# Schematic_v13.net
KiCad netlist of a schematic drawn in EAGLE
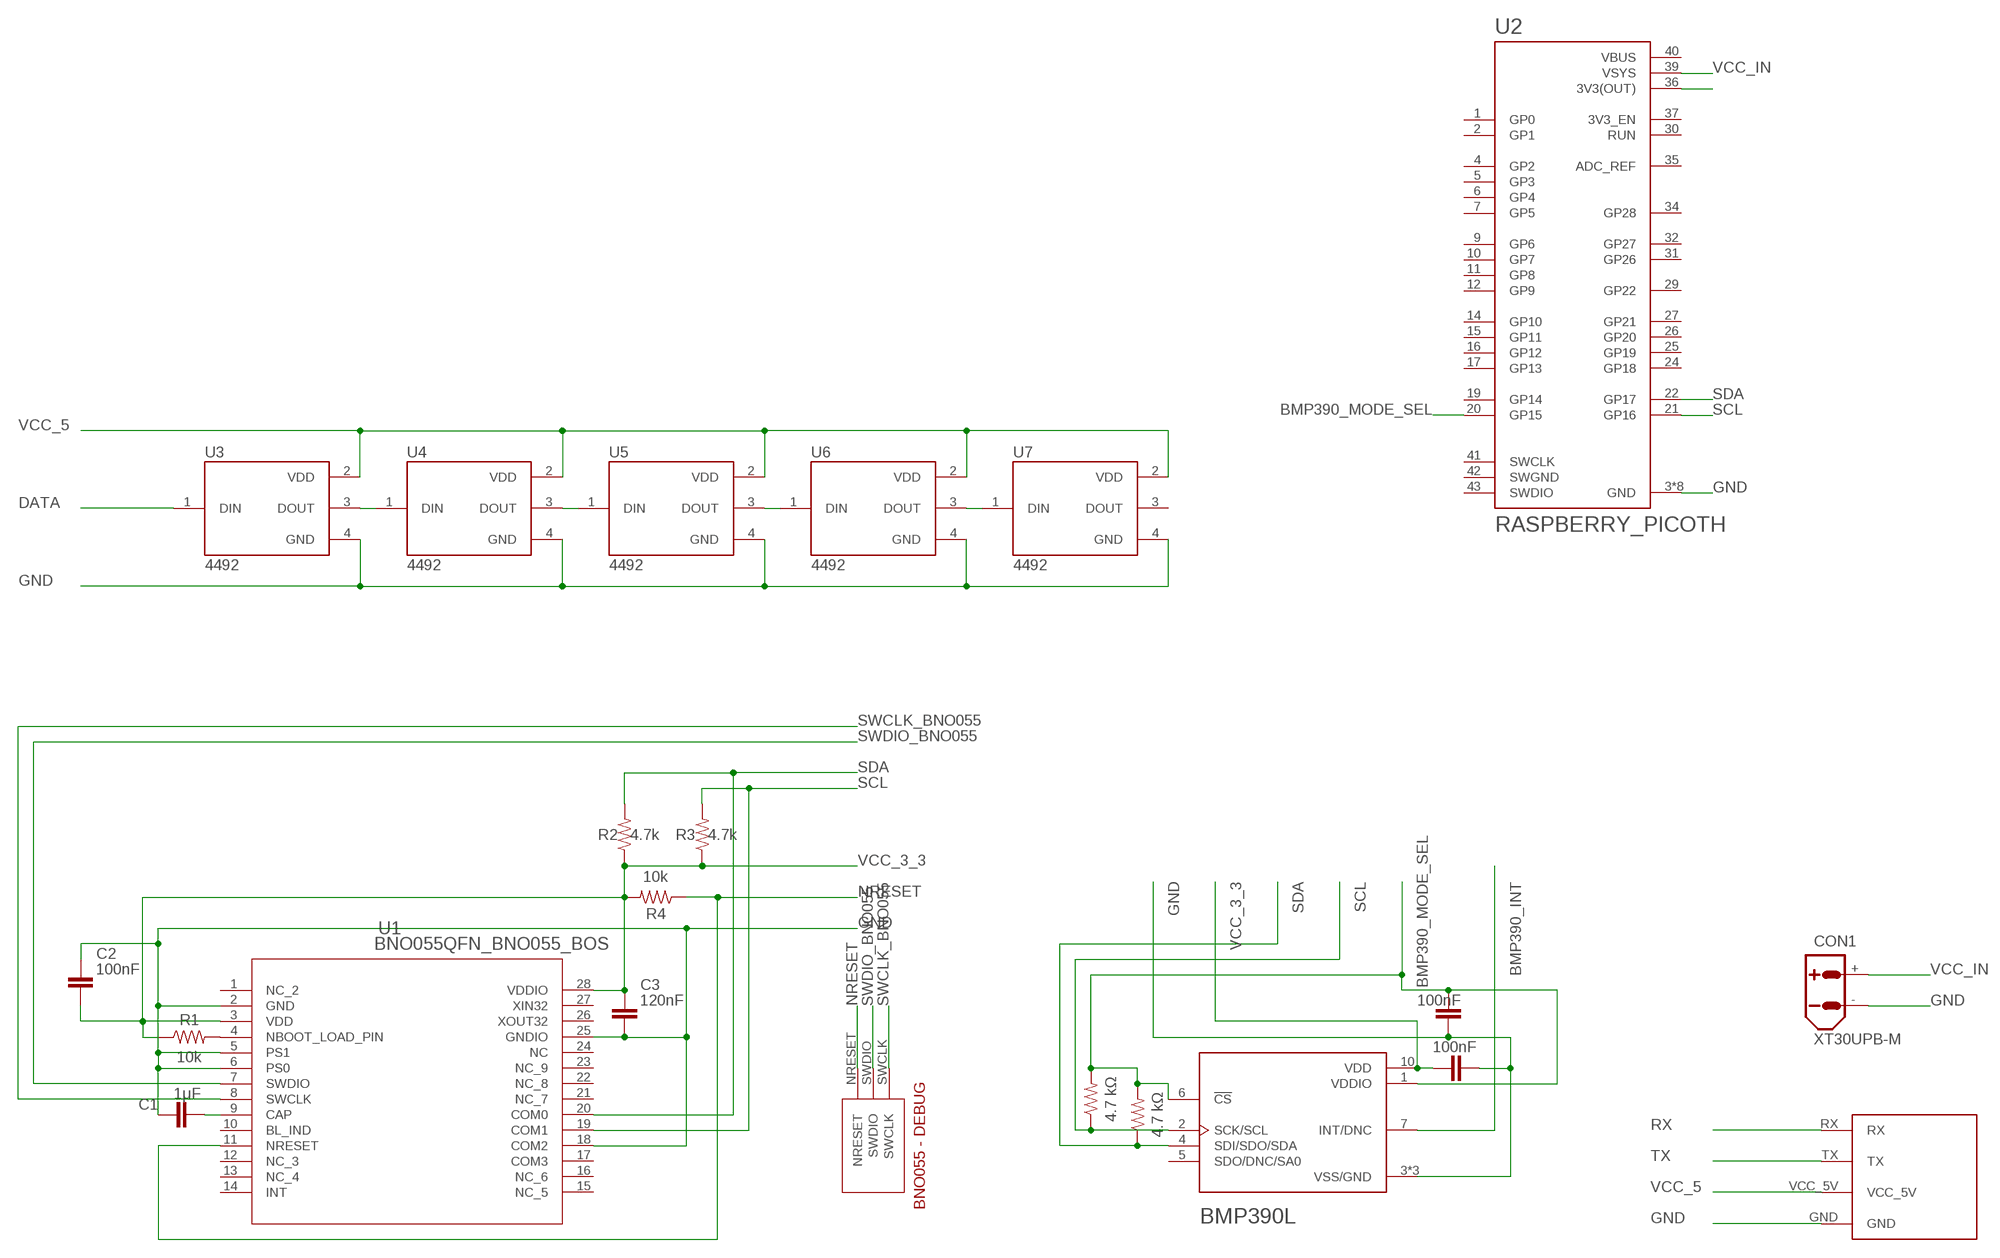
[diagram p0: schematic, sheet 1]

(export (version "E")
  (design (tool "Eeschema 10.0.6"))
  (components
    (comp (ref "C1")
      (value "1μF")
      (footprint "eagle-import:CAPC3216X135")
      (libsource (lib "eagle-import") (part "CCHIP-1206(3216-METRIC)_"))
    )
    (comp (ref "C2")
      (value "100nF")
      (footprint "eagle-import:CAPC3216X135")
      (libsource (lib "eagle-import") (part "CCHIP-1206(3216-METRIC)_"))
    )
    (comp (ref "C3")
      (value "120nF")
      (footprint "eagle-import:CAPC3216X135")
      (libsource (lib "eagle-import") (part "CCHIP-1206(3216-METRIC)_"))
    )
    (comp (ref "C4")
      (value "100nF")
      (footprint "eagle-import:CAPC3216X135")
      (libsource (lib "eagle-import") (part "CCHIP-1206(3216-METRIC)_"))
    )
    (comp (ref "C5")
      (value "100nF")
      (footprint "eagle-import:CAPC3216X135")
      (libsource (lib "eagle-import") (part "CCHIP-1206(3216-METRIC)_"))
    )
    (comp (ref "CON1")
      (value "XT30UPB-M")
      (footprint "eagle-import:XT30UPB-M")
      (libsource (lib "eagle-import") (part "XT30UPB-M"))
    )
    (comp (ref "R1")
      (value "10k")
      (footprint "eagle-import:RESC3216X70")
      (libsource (lib "eagle-import") (part "R-USCHIP-1206(3216-METRIC)_"))
    )
    (comp (ref "R2")
      (value "4.7k")
      (footprint "eagle-import:RESC3216X70")
      (libsource (lib "eagle-import") (part "R-USCHIP-1206(3216-METRIC)_"))
    )
    (comp (ref "R3")
      (value "4.7k")
      (footprint "eagle-import:RESC3216X70")
      (libsource (lib "eagle-import") (part "R-USCHIP-1206(3216-METRIC)_"))
    )
    (comp (ref "R4")
      (value "10k")
      (footprint "eagle-import:RESC3216X70")
      (libsource (lib "eagle-import") (part "R-USCHIP-1206(3216-METRIC)_"))
    )
    (comp (ref "R5")
      (value "4.7 kΩ")
      (footprint "eagle-import:RESC3216X70")
      (libsource (lib "eagle-import") (part "R-USCHIP-1206(3216-METRIC)_"))
    )
    (comp (ref "R6")
      (value "4.7 kΩ")
      (footprint "eagle-import:RESC3216X70")
      (libsource (lib "eagle-import") (part "R-USCHIP-1206(3216-METRIC)_"))
    )
    (comp (ref "U$1")
      (value "EP1")
      (footprint "eagle-import:EP1_MODEL")
      (libsource (lib "eagle-import") (part "EP1"))
    )
    (comp (ref "U$2")
      (value "BNO055_DEBUG_PORT")
      (footprint "eagle-import:BNO05_FOOTPRINT")
      (libsource (lib "eagle-import") (part "BNO055_DEBUG_PORT"))
    )
    (comp (ref "U1")
      (value "BNO055QFN_BNO055_BOS")
      (footprint "eagle-import:QFN_BNO055_BOS")
      (fields
        (field (name "MANUFACTURER_PART_NUMBER") "BNO055")
        (field (name "COPYRIGHT") "Copyright (C) 2024 Ultra Librarian. All rights reserved.")
      )
      (libsource (lib "eagle-import") (part "BNO055QFN_BNO055_BOS"))
    )
    (comp (ref "U2")
      (value "RASPBERRY_PICOTH")
      (footprint "eagle-import:PICO-PKG-TH")
      (libsource (lib "eagle-import") (part "RASPBERRY_PICOTH"))
    )
    (comp (ref "U3")
      (value "4492")
      (footprint "eagle-import:LED_4492")
      (fields (field (name "MF") "Adafruit"))
      (libsource (lib "eagle-import") (part "4492"))
    )
    (comp (ref "U4")
      (value "4492")
      (footprint "eagle-import:LED_4492")
      (fields (field (name "MF") "Adafruit"))
      (libsource (lib "eagle-import") (part "4492"))
    )
    (comp (ref "U5")
      (value "4492")
      (footprint "eagle-import:LED_4492")
      (fields (field (name "MF") "Adafruit"))
      (libsource (lib "eagle-import") (part "4492"))
    )
    (comp (ref "U6")
      (value "4492")
      (footprint "eagle-import:LED_4492")
      (fields (field (name "MF") "Adafruit"))
      (libsource (lib "eagle-import") (part "4492"))
    )
    (comp (ref "U7")
      (value "4492")
      (footprint "eagle-import:LED_4492")
      (fields (field (name "MF") "Adafruit"))
      (libsource (lib "eagle-import") (part "4492"))
    )
    (comp (ref "U11")
      (value "BMP390L")
      (footprint "eagle-import:XDCR_BMP390L")
      (fields (field (name "MF") "Bosch Sensortec"))
      (libsource (lib "eagle-import") (part "BMP390L"))
    )
  )
  (nets
    (net (code "1") (name "/BMP390_INT") (class "Default")
      (node (ref "U11") (pin "7") (pinfunction "INT/DNC_7") (pintype "output"))
    )
    (net (code "2") (name "/BMP390_MODE_SEL") (class "Default")
      (node (ref "C5") (pin "1") (pinfunction "1_1") (pintype "passive"))
      (node (ref "R5") (pin "2") (pinfunction "2_2") (pintype "passive"))
      (node (ref "R6") (pin "2") (pinfunction "2_2") (pintype "passive"))
      (node (ref "U11") (pin "1") (pinfunction "VDDIO_1") (pintype "power_in"))
      (node (ref "U11") (pin "6") (pinfunction "~{CS}_6") (pintype "input"))
      (node (ref "U2") (pin "20") (pinfunction "GP15_20") (pintype "bidirectional"))
    )
    (net (code "3") (name "/DATA") (class "Default")
      (node (ref "U3") (pin "1") (pinfunction "DIN_1") (pintype "input"))
    )
    (net (code "4") (name "/GND") (class "Default")
      (node (ref "C1") (pin "1") (pinfunction "1_1") (pintype "passive"))
      (node (ref "C2") (pin "1") (pinfunction "1_1") (pintype "passive"))
      (node (ref "C3") (pin "2") (pinfunction "2_2") (pintype "passive"))
      (node (ref "C4") (pin "2") (pinfunction "2_2") (pintype "passive"))
      (node (ref "C5") (pin "2") (pinfunction "2_2") (pintype "passive"))
      (node (ref "CON1") (pin "-") (pinfunction "-_-") (pintype "power_in"))
      (node (ref "U$1") (pin "GND") (pinfunction "GND_GND") (pintype "bidirectional"))
      (node (ref "U1") (pin "18") (pinfunction "COM2_18") (pintype "bidirectional"))
      (node (ref "U1") (pin "2") (pinfunction "GND_2") (pintype "passive"))
      (node (ref "U1") (pin "25") (pinfunction "GNDIO_25") (pintype "passive"))
      (node (ref "U1") (pin "5") (pinfunction "PS1_5") (pintype "input"))
      (node (ref "U1") (pin "6") (pinfunction "PS0_6") (pintype "input"))
      (node (ref "U11") (pin "3") (pinfunction "VSS/GND_3") (pintype "power_in"))
      (node (ref "U11") (pin "8") (pinfunction "VSS/GND_8") (pintype "power_in"))
      (node (ref "U11") (pin "9") (pinfunction "VSS/GND_9") (pintype "power_in"))
      (node (ref "U2") (pin "13") (pinfunction "GND_13") (pintype "power_in"))
      (node (ref "U2") (pin "18") (pinfunction "GND_18") (pintype "power_in"))
      (node (ref "U2") (pin "23") (pinfunction "GND_23") (pintype "power_in"))
      (node (ref "U2") (pin "28") (pinfunction "GND_28") (pintype "power_in"))
      (node (ref "U2") (pin "3") (pinfunction "GND_3") (pintype "power_in"))
      (node (ref "U2") (pin "33") (pinfunction "GND_33") (pintype "power_in"))
      (node (ref "U2") (pin "38") (pinfunction "GND_38") (pintype "power_in"))
      (node (ref "U2") (pin "8") (pinfunction "GND_8") (pintype "power_in"))
      (node (ref "U3") (pin "4") (pinfunction "GND_4") (pintype "power_in"))
      (node (ref "U4") (pin "4") (pinfunction "GND_4") (pintype "power_in"))
      (node (ref "U5") (pin "4") (pinfunction "GND_4") (pintype "power_in"))
      (node (ref "U6") (pin "4") (pinfunction "GND_4") (pintype "power_in"))
      (node (ref "U7") (pin "4") (pinfunction "GND_4") (pintype "power_in"))
    )
    (net (code "5") (name "/NRESET") (class "Default")
      (node (ref "R4") (pin "1") (pinfunction "1_1") (pintype "passive"))
      (node (ref "U$2") (pin "NRESET") (pinfunction "NRESET_NRESET") (pintype "bidirectional"))
      (node (ref "U1") (pin "11") (pinfunction "NRESET_11") (pintype "passive"))
    )
    (net (code "6") (name "/RX") (class "Default")
      (node (ref "U$1") (pin "RX") (pinfunction "RX_RX") (pintype "bidirectional"))
    )
    (net (code "7") (name "/SCL") (class "Default")
      (node (ref "R3") (pin "2") (pinfunction "2_2") (pintype "passive"))
      (node (ref "R5") (pin "1") (pinfunction "1_1") (pintype "passive"))
      (node (ref "U1") (pin "19") (pinfunction "COM1_19") (pintype "bidirectional"))
      (node (ref "U11") (pin "2") (pinfunction "SCK/SCL_2") (pintype "input"))
      (node (ref "U2") (pin "21") (pinfunction "GP16_21") (pintype "bidirectional"))
    )
    (net (code "8") (name "/SDA") (class "Default")
      (node (ref "R2") (pin "2") (pinfunction "2_2") (pintype "passive"))
      (node (ref "R6") (pin "1") (pinfunction "1_1") (pintype "passive"))
      (node (ref "U1") (pin "20") (pinfunction "COM0_20") (pintype "bidirectional"))
      (node (ref "U11") (pin "4") (pinfunction "SDI/SDO/SDA_4") (pintype "bidirectional"))
      (node (ref "U2") (pin "22") (pinfunction "GP17_22") (pintype "bidirectional"))
    )
    (net (code "9") (name "/SWCLK_BNO055") (class "Default")
      (node (ref "U$2") (pin "SWCLK") (pinfunction "SWCLK_SWCLK") (pintype "bidirectional"))
      (node (ref "U1") (pin "8") (pinfunction "SWCLK_8") (pintype "input"))
    )
    (net (code "10") (name "/SWDIO_BNO055") (class "Default")
      (node (ref "U$2") (pin "SWDIO") (pinfunction "SWDIO_SWDIO") (pintype "bidirectional"))
      (node (ref "U1") (pin "7") (pinfunction "SWDIO_7") (pintype "bidirectional"))
    )
    (net (code "11") (name "/SWGND") (class "Default")
      (node (ref "U2") (pin "42") (pinfunction "SWGND_42") (pintype "power_in"))
    )
    (net (code "12") (name "/TX") (class "Default")
      (node (ref "U$1") (pin "TX") (pinfunction "TX_TX") (pintype "bidirectional"))
    )
    (net (code "13") (name "/VBUS") (class "Default")
      (node (ref "U2") (pin "40") (pinfunction "VBUS_40") (pintype "power_in"))
    )
    (net (code "14") (name "/VCC_3_3") (class "Default")
      (node (ref "C2") (pin "2") (pinfunction "2_2") (pintype "passive"))
      (node (ref "C3") (pin "1") (pinfunction "1_1") (pintype "passive"))
      (node (ref "C4") (pin "1") (pinfunction "1_1") (pintype "passive"))
      (node (ref "R1") (pin "1") (pinfunction "1_1") (pintype "passive"))
      (node (ref "R2") (pin "1") (pinfunction "1_1") (pintype "passive"))
      (node (ref "R3") (pin "1") (pinfunction "1_1") (pintype "passive"))
      (node (ref "R4") (pin "2") (pinfunction "2_2") (pintype "passive"))
      (node (ref "U1") (pin "28") (pinfunction "VDDIO_28") (pintype "power_in"))
      (node (ref "U1") (pin "3") (pinfunction "VDD_3") (pintype "power_in"))
      (node (ref "U11") (pin "10") (pinfunction "VDD_10") (pintype "power_in"))
      (node (ref "U2") (pin "36") (pinfunction "3V3(OUT)_36") (pintype "power_in"))
    )
    (net (code "15") (name "/VCC_5") (class "Default")
      (node (ref "U$1") (pin "VCC_5V") (pinfunction "VCC_5V_VCC_5V") (pintype "bidirectional"))
      (node (ref "U3") (pin "2") (pinfunction "VDD_2") (pintype "power_in"))
      (node (ref "U4") (pin "2") (pinfunction "VDD_2") (pintype "power_in"))
      (node (ref "U5") (pin "2") (pinfunction "VDD_2") (pintype "power_in"))
      (node (ref "U6") (pin "2") (pinfunction "VDD_2") (pintype "power_in"))
      (node (ref "U7") (pin "2") (pinfunction "VDD_2") (pintype "power_in"))
    )
    (net (code "16") (name "/VCC_IN") (class "Default")
      (node (ref "CON1") (pin "+") (pinfunction "+_+") (pintype "power_in"))
      (node (ref "U2") (pin "39") (pinfunction "VSYS_39") (pintype "power_in"))
    )
    (net (code "17") (name "Net-(U1-CAP)") (class "Default")
      (node (ref "C1") (pin "2") (pinfunction "2_2") (pintype "passive"))
      (node (ref "U1") (pin "9") (pinfunction "CAP_9") (pintype "passive"))
    )
    (net (code "18") (name "Net-(U1-NBOOT_LOAD_PIN)") (class "Default")
      (node (ref "R1") (pin "2") (pinfunction "2_2") (pintype "passive"))
      (node (ref "U1") (pin "4") (pinfunction "NBOOT_LOAD_PIN_4") (pintype "input"))
    )
    (net (code "19") (name "Net-(U3-DOUT)") (class "Default")
      (node (ref "U3") (pin "3") (pinfunction "DOUT_3") (pintype "output"))
      (node (ref "U4") (pin "1") (pinfunction "DIN_1") (pintype "input"))
    )
    (net (code "20") (name "Net-(U4-DOUT)") (class "Default")
      (node (ref "U4") (pin "3") (pinfunction "DOUT_3") (pintype "output"))
      (node (ref "U5") (pin "1") (pinfunction "DIN_1") (pintype "input"))
    )
    (net (code "21") (name "Net-(U5-DOUT)") (class "Default")
      (node (ref "U5") (pin "3") (pinfunction "DOUT_3") (pintype "output"))
      (node (ref "U6") (pin "1") (pinfunction "DIN_1") (pintype "input"))
    )
    (net (code "22") (name "Net-(U6-DOUT)") (class "Default")
      (node (ref "U6") (pin "3") (pinfunction "DOUT_3") (pintype "output"))
      (node (ref "U7") (pin "1") (pinfunction "DIN_1") (pintype "input"))
    )
    (net (code "23") (name "unconnected-(U1-BL_IND-Pad10)") (class "Default")
      (node (ref "U1") (pin "10") (pinfunction "BL_IND_10") (pintype "output"))
    )
    (net (code "24") (name "unconnected-(U1-COM3-Pad17)") (class "Default")
      (node (ref "U1") (pin "17") (pinfunction "COM3_17") (pintype "input"))
    )
    (net (code "25") (name "unconnected-(U1-INT-Pad14)") (class "Default")
      (node (ref "U1") (pin "14") (pinfunction "INT_14") (pintype "output"))
    )
    (net (code "26") (name "unconnected-(U1-NC-Pad24)") (class "Default")
      (node (ref "U1") (pin "24") (pinfunction "NC_24") (pintype "no_connect"))
    )
    (net (code "27") (name "unconnected-(U1-NC_2-Pad1)") (class "Default")
      (node (ref "U1") (pin "1") (pinfunction "NC_2_1") (pintype "no_connect"))
    )
    (net (code "28") (name "unconnected-(U1-NC_3-Pad12)") (class "Default")
      (node (ref "U1") (pin "12") (pinfunction "NC_3_12") (pintype "no_connect"))
    )
    (net (code "29") (name "unconnected-(U1-NC_4-Pad13)") (class "Default")
      (node (ref "U1") (pin "13") (pinfunction "NC_4_13") (pintype "no_connect"))
    )
    (net (code "30") (name "unconnected-(U1-NC_5-Pad15)") (class "Default")
      (node (ref "U1") (pin "15") (pinfunction "NC_5_15") (pintype "no_connect"))
    )
    (net (code "31") (name "unconnected-(U1-NC_6-Pad16)") (class "Default")
      (node (ref "U1") (pin "16") (pinfunction "NC_6_16") (pintype "no_connect"))
    )
    (net (code "32") (name "unconnected-(U1-NC_7-Pad21)") (class "Default")
      (node (ref "U1") (pin "21") (pinfunction "NC_7_21") (pintype "no_connect"))
    )
    (net (code "33") (name "unconnected-(U1-NC_8-Pad22)") (class "Default")
      (node (ref "U1") (pin "22") (pinfunction "NC_8_22") (pintype "no_connect"))
    )
    (net (code "34") (name "unconnected-(U1-NC_9-Pad23)") (class "Default")
      (node (ref "U1") (pin "23") (pinfunction "NC_9_23") (pintype "no_connect"))
    )
    (net (code "35") (name "unconnected-(U1-XIN32-Pad27)") (class "Default")
      (node (ref "U1") (pin "27") (pinfunction "XIN32_27") (pintype "input"))
    )
    (net (code "36") (name "unconnected-(U1-XOUT32-Pad26)") (class "Default")
      (node (ref "U1") (pin "26") (pinfunction "XOUT32_26") (pintype "output"))
    )
    (net (code "37") (name "unconnected-(U2-3V3_EN-Pad37)") (class "Default")
      (node (ref "U2") (pin "37") (pinfunction "3V3_EN_37") (pintype "input"))
    )
    (net (code "38") (name "unconnected-(U2-ADC_REF-Pad35)") (class "Default")
      (node (ref "U2") (pin "35") (pinfunction "ADC_REF_35") (pintype "input"))
    )
    (net (code "39") (name "unconnected-(U2-GP0-Pad1)") (class "Default")
      (node (ref "U2") (pin "1") (pinfunction "GP0_1") (pintype "bidirectional"))
    )
    (net (code "40") (name "unconnected-(U2-GP1-Pad2)") (class "Default")
      (node (ref "U2") (pin "2") (pinfunction "GP1_2") (pintype "bidirectional"))
    )
    (net (code "41") (name "unconnected-(U2-GP2-Pad4)") (class "Default")
      (node (ref "U2") (pin "4") (pinfunction "GP2_4") (pintype "bidirectional"))
    )
    (net (code "42") (name "unconnected-(U2-GP3-Pad5)") (class "Default")
      (node (ref "U2") (pin "5") (pinfunction "GP3_5") (pintype "bidirectional"))
    )
    (net (code "43") (name "unconnected-(U2-GP4-Pad6)") (class "Default")
      (node (ref "U2") (pin "6") (pinfunction "GP4_6") (pintype "bidirectional"))
    )
    (net (code "44") (name "unconnected-(U2-GP5-Pad7)") (class "Default")
      (node (ref "U2") (pin "7") (pinfunction "GP5_7") (pintype "bidirectional"))
    )
    (net (code "45") (name "unconnected-(U2-GP6-Pad9)") (class "Default")
      (node (ref "U2") (pin "9") (pinfunction "GP6_9") (pintype "bidirectional"))
    )
    (net (code "46") (name "unconnected-(U2-GP7-Pad10)") (class "Default")
      (node (ref "U2") (pin "10") (pinfunction "GP7_10") (pintype "bidirectional"))
    )
    (net (code "47") (name "unconnected-(U2-GP8-Pad11)") (class "Default")
      (node (ref "U2") (pin "11") (pinfunction "GP8_11") (pintype "bidirectional"))
    )
    (net (code "48") (name "unconnected-(U2-GP9-Pad12)") (class "Default")
      (node (ref "U2") (pin "12") (pinfunction "GP9_12") (pintype "bidirectional"))
    )
    (net (code "49") (name "unconnected-(U2-GP10-Pad14)") (class "Default")
      (node (ref "U2") (pin "14") (pinfunction "GP10_14") (pintype "bidirectional"))
    )
    (net (code "50") (name "unconnected-(U2-GP11-Pad15)") (class "Default")
      (node (ref "U2") (pin "15") (pinfunction "GP11_15") (pintype "bidirectional"))
    )
    (net (code "51") (name "unconnected-(U2-GP12-Pad16)") (class "Default")
      (node (ref "U2") (pin "16") (pinfunction "GP12_16") (pintype "bidirectional"))
    )
    (net (code "52") (name "unconnected-(U2-GP13-Pad17)") (class "Default")
      (node (ref "U2") (pin "17") (pinfunction "GP13_17") (pintype "bidirectional"))
    )
    (net (code "53") (name "unconnected-(U2-GP14-Pad19)") (class "Default")
      (node (ref "U2") (pin "19") (pinfunction "GP14_19") (pintype "bidirectional"))
    )
    (net (code "54") (name "unconnected-(U2-GP18-Pad24)") (class "Default")
      (node (ref "U2") (pin "24") (pinfunction "GP18_24") (pintype "bidirectional"))
    )
    (net (code "55") (name "unconnected-(U2-GP19-Pad25)") (class "Default")
      (node (ref "U2") (pin "25") (pinfunction "GP19_25") (pintype "bidirectional"))
    )
    (net (code "56") (name "unconnected-(U2-GP20-Pad26)") (class "Default")
      (node (ref "U2") (pin "26") (pinfunction "GP20_26") (pintype "bidirectional"))
    )
    (net (code "57") (name "unconnected-(U2-GP21-Pad27)") (class "Default")
      (node (ref "U2") (pin "27") (pinfunction "GP21_27") (pintype "bidirectional"))
    )
    (net (code "58") (name "unconnected-(U2-GP22-Pad29)") (class "Default")
      (node (ref "U2") (pin "29") (pinfunction "GP22_29") (pintype "bidirectional"))
    )
    (net (code "59") (name "unconnected-(U2-GP26-Pad31)") (class "Default")
      (node (ref "U2") (pin "31") (pinfunction "GP26_31") (pintype "bidirectional"))
    )
    (net (code "60") (name "unconnected-(U2-GP27-Pad32)") (class "Default")
      (node (ref "U2") (pin "32") (pinfunction "GP27_32") (pintype "bidirectional"))
    )
    (net (code "61") (name "unconnected-(U2-GP28-Pad34)") (class "Default")
      (node (ref "U2") (pin "34") (pinfunction "GP28_34") (pintype "bidirectional"))
    )
    (net (code "62") (name "unconnected-(U2-RUN-Pad30)") (class "Default")
      (node (ref "U2") (pin "30") (pinfunction "RUN_30") (pintype "input"))
    )
    (net (code "63") (name "unconnected-(U2-SWCLK-Pad41)") (class "Default")
      (node (ref "U2") (pin "41") (pinfunction "SWCLK_41") (pintype "input"))
    )
    (net (code "64") (name "unconnected-(U2-SWDIO-Pad43)") (class "Default")
      (node (ref "U2") (pin "43") (pinfunction "SWDIO_43") (pintype "bidirectional"))
    )
    (net (code "65") (name "unconnected-(U7-DOUT-Pad3)") (class "Default")
      (node (ref "U7") (pin "3") (pinfunction "DOUT_3") (pintype "output"))
    )
    (net (code "66") (name "unconnected-(U11-SDO{slash}DNC{slash}SA0-Pad5)") (class "Default")
      (node (ref "U11") (pin "5") (pinfunction "SDO/DNC/SA0_5") (pintype "bidirectional"))
    )
  )
)
